# FT232RL_Model_with_USB-C.net
KiCad netlist of a schematic drawn in Altium Designer
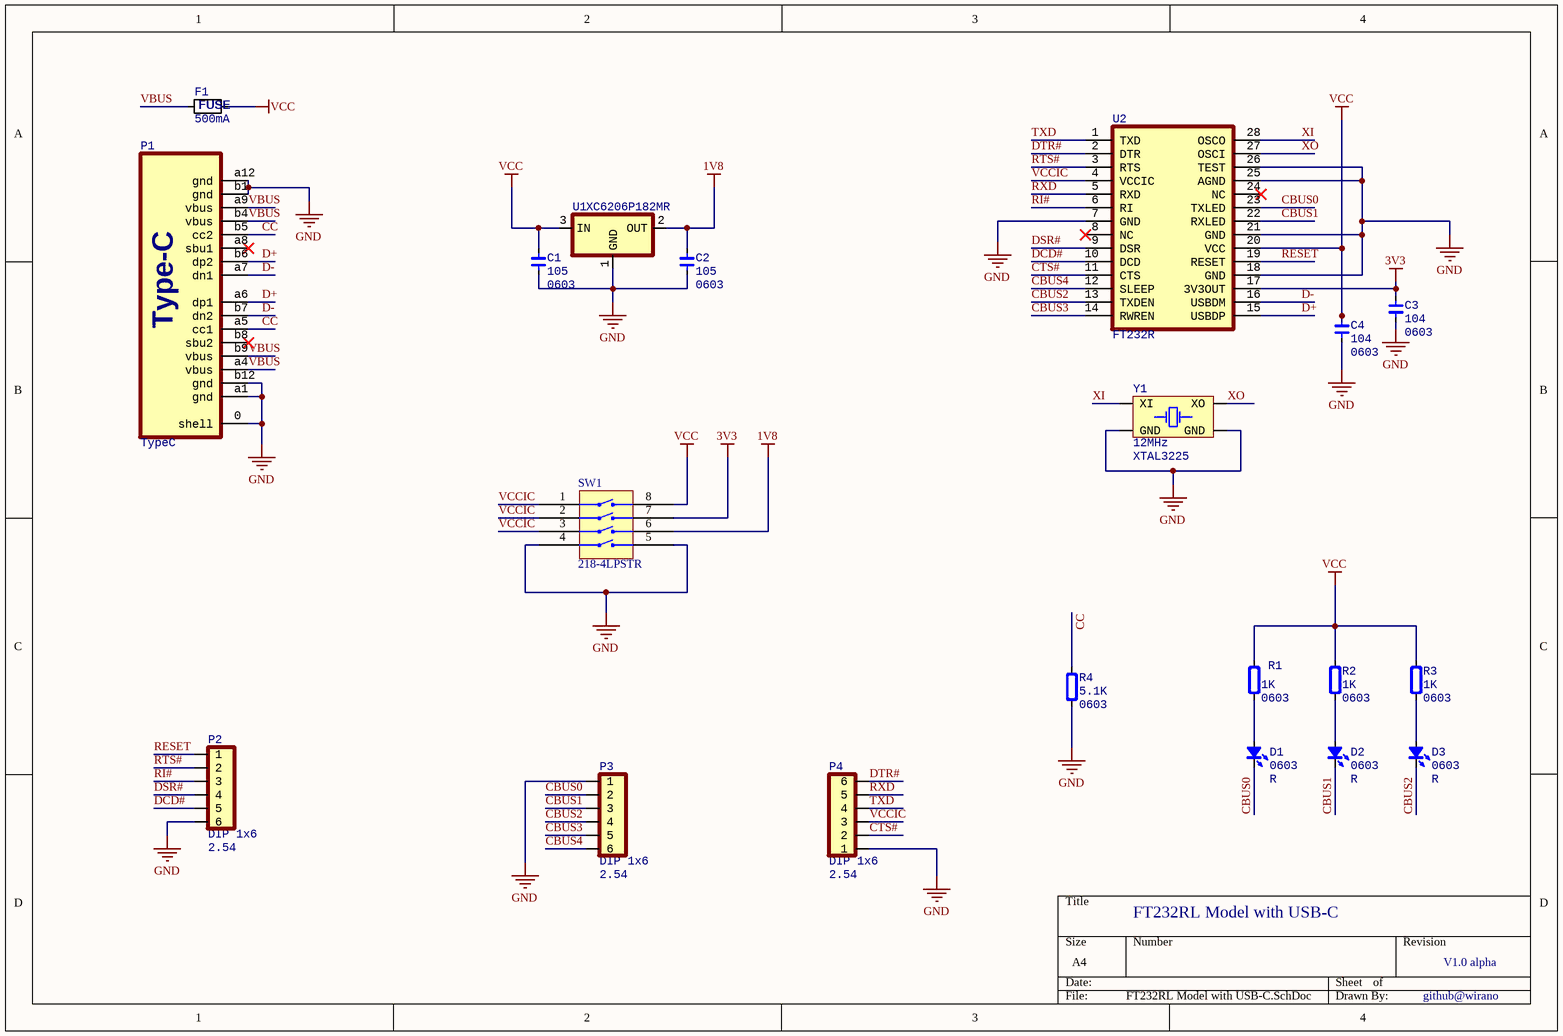
[diagram p0: FT232RL Model with USB-C.SchDoc]

(export (version "E")
  (design (tool "Eeschema 10.0.6"))
  (components
    (comp (ref "C1")
      (value "105")
      (footprint "CAP 0603/1608")
      (description "Capacitor")
      (fields (field (name "TYPE") "0603") (field (name "Comment") "C0603"))
      (libsource (lib "adlib") (part "Cap_0603"))
    )
    (comp (ref "C2")
      (value "105")
      (footprint "CAP 0603/1608")
      (description "Capacitor")
      (fields (field (name "TYPE") "0603") (field (name "Comment") "C0603"))
      (libsource (lib "adlib") (part "Cap_0603"))
    )
    (comp (ref "C3")
      (value "104")
      (footprint "CAP 0603/1608")
      (description "Capacitor")
      (fields (field (name "TYPE") "0603") (field (name "Comment") "C0603"))
      (libsource (lib "") (part "Cap_0603_1"))
    )
    (comp (ref "C4")
      (value "104")
      (footprint "CAP 0603/1608")
      (description "Capacitor")
      (fields (field (name "TYPE") "0603") (field (name "Comment") "C0603"))
      (libsource (lib "adlib") (part "Cap_0603"))
    )
    (comp (ref "D1")
      (value "R")
      (footprint "LED_0603_RED")
      (description "LED")
      (fields (field (name "TYPE") "0603"))
      (libsource (lib "adlib") (part "LED_0603"))
    )
    (comp (ref "D2")
      (value "R")
      (footprint "LED_0603_RED")
      (description "LED")
      (fields (field (name "TYPE") "0603"))
      (libsource (lib "adlib") (part "LED_0603"))
    )
    (comp (ref "D3")
      (value "R")
      (footprint "LED_0603_RED")
      (description "LED")
      (fields (field (name "TYPE") "0603"))
      (libsource (lib "adlib") (part "LED_0603"))
    )
    (comp (ref "F1")
      (value "500mA")
      (footprint "PPTC_0603")
      (description "resettable fuse")
      (libsource (lib "adlib") (part "Fuse"))
    )
    (comp (ref "P1")
      (value "TypeC")
      (footprint "USB_TypeC")
      (description "USB type-c cable")
      (libsource (lib "adlib") (part "USB_TypeC"))
    )
    (comp (ref "P2")
      (value "2.54")
      (footprint "HDR1X6_2.54_180")
      (description "Header")
      (fields (field (name "TYPE") "DIP 1x6") (field (name "Comment") "DIP 1x6"))
      (libsource (lib "adlib") (part "HDR1x6_2.54"))
    )
    (comp (ref "P3")
      (value "2.54")
      (footprint "HDR1X6_2.54_180")
      (description "Header")
      (fields (field (name "TYPE") "DIP 1x6") (field (name "Comment") "DIP 1x6"))
      (libsource (lib "adlib") (part "HDR1x6_2.54"))
    )
    (comp (ref "P4")
      (value "2.54")
      (footprint "HDR1X6_2.54_90")
      (description "Header")
      (fields (field (name "TYPE") "DIP 1x6") (field (name "Comment") "DIP 1x6"))
      (libsource (lib "") (part "HDR1x6_2.54_1"))
    )
    (comp (ref "R1")
      (value "1K")
      (footprint "RES 0603/1608")
      (description "SMT Resistor")
      (fields (field (name "TYPE") "0603") (field (name "Comment") "R0603"))
      (libsource (lib "adlib") (part "Res_0603"))
    )
    (comp (ref "R2")
      (value "1K")
      (footprint "RES 0603/1608")
      (description "SMT Resistor")
      (fields (field (name "TYPE") "0603") (field (name "Comment") "R0603"))
      (libsource (lib "adlib") (part "Res_0603"))
    )
    (comp (ref "R3")
      (value "1K")
      (footprint "RES 0603/1608")
      (description "SMT Resistor")
      (fields (field (name "TYPE") "0603") (field (name "Comment") "R0603"))
      (libsource (lib "adlib") (part "Res_0603"))
    )
    (comp (ref "R4")
      (value "5.1K")
      (footprint "RES 0603/1608")
      (description "SMT Resistor")
      (fields (field (name "TYPE") "0603") (field (name "Comment") "R0603"))
      (libsource (lib "adlib") (part "Res_0603"))
    )
    (comp (ref "SW1")
      (value "218-4LPSTR")
      (footprint "CTS 218-4LPJ")
      (description "SWITCH SLIDE DIP SPST 25MA 24V")
      (fields
        (field (name "MANUFACTURER") "CTS Electrocomponents")
        (field (name "LASTUPDATED") "20/1/4 周六 18:53:14")
      )
      (libsource (lib "Celestial Altium Library - altium_library") (part "DIP SW 4P"))
    )
    (comp (ref "U1")
      (value "XC6206P182MR")
      (footprint "_SOT23-3")
      (description "Regulator LDO")
      (libsource (lib "adlib") (part "XC6206P332MR"))
    )
    (comp (ref "U2")
      (value "FT232R")
      (footprint "_SSOP_E210_P0.65_28")
      (description "USB to UART Converter")
      (libsource (lib "adlib") (part "FT232R"))
    )
    (comp (ref "Y1")
      (value "12MHz")
      (footprint "XT_3225_4")
      (description "Crystal Oscillator")
      (fields (field (name "TYPE") "XTAL3225") (field (name "Comment") "XTAL3225"))
      (libsource (lib "adlib") (part "XTAL_3225_4P"))
    )
  )
  (nets
    (net (code "1") (name "/CBUS0") (class "Default")
      (node (ref "D1") (pin "2") (pinfunction "K_2") (pintype "passive"))
      (node (ref "P3") (pin "2") (pinfunction "2_2") (pintype "passive"))
      (node (ref "U2") (pin "23") (pinfunction "TXLED_23") (pintype "passive"))
    )
    (net (code "2") (name "/CBUS1") (class "Default")
      (node (ref "D2") (pin "2") (pinfunction "K_2") (pintype "passive"))
      (node (ref "P3") (pin "3") (pinfunction "3_3") (pintype "passive"))
      (node (ref "U2") (pin "22") (pinfunction "RXLED_22") (pintype "passive"))
    )
    (net (code "3") (name "/CBUS2") (class "Default")
      (node (ref "D3") (pin "2") (pinfunction "K_2") (pintype "passive"))
      (node (ref "P3") (pin "4") (pinfunction "4_4") (pintype "passive"))
      (node (ref "U2") (pin "13") (pinfunction "TXDEN_13") (pintype "passive"))
    )
    (net (code "4") (name "/CBUS3") (class "Default")
      (node (ref "P3") (pin "5") (pinfunction "5_5") (pintype "passive"))
      (node (ref "U2") (pin "14") (pinfunction "RWREN_14") (pintype "passive"))
    )
    (net (code "5") (name "/CBUS4") (class "Default")
      (node (ref "P3") (pin "6") (pinfunction "6_6") (pintype "passive"))
      (node (ref "U2") (pin "12") (pinfunction "SLEEP_12") (pintype "passive"))
    )
    (net (code "6") (name "/CC") (class "Default")
      (node (ref "P1") (pin "a5") (pinfunction "cc1_a5") (pintype "passive"))
      (node (ref "P1") (pin "b5") (pinfunction "cc2_b5") (pintype "passive"))
      (node (ref "R4") (pin "2") (pinfunction "2_2") (pintype "passive"))
    )
    (net (code "7") (name "/CTS#") (class "Default")
      (node (ref "P4") (pin "2") (pinfunction "2_2") (pintype "passive"))
      (node (ref "U2") (pin "11") (pinfunction "CTS_11") (pintype "passive"))
    )
    (net (code "8") (name "/D+") (class "Default")
      (node (ref "P1") (pin "a6") (pinfunction "dp1_a6") (pintype "passive"))
      (node (ref "P1") (pin "b6") (pinfunction "dp2_b6") (pintype "passive"))
      (node (ref "U2") (pin "15") (pinfunction "USBDP_15") (pintype "passive"))
    )
    (net (code "9") (name "/D-") (class "Default")
      (node (ref "P1") (pin "a7") (pinfunction "dn1_a7") (pintype "passive"))
      (node (ref "P1") (pin "b7") (pinfunction "dn2_b7") (pintype "passive"))
      (node (ref "U2") (pin "16") (pinfunction "USBDM_16") (pintype "passive"))
    )
    (net (code "10") (name "/DCD#") (class "Default")
      (node (ref "P2") (pin "5") (pinfunction "5_5") (pintype "passive"))
      (node (ref "U2") (pin "10") (pinfunction "DCD_10") (pintype "passive"))
    )
    (net (code "11") (name "/DSR#") (class "Default")
      (node (ref "P2") (pin "4") (pinfunction "4_4") (pintype "passive"))
      (node (ref "U2") (pin "9") (pinfunction "DSR_9") (pintype "passive"))
    )
    (net (code "12") (name "/DTR#") (class "Default")
      (node (ref "P4") (pin "6") (pinfunction "6_6") (pintype "passive"))
      (node (ref "U2") (pin "2") (pinfunction "DTR_2") (pintype "passive"))
    )
    (net (code "13") (name "/RESET") (class "Default")
      (node (ref "P2") (pin "1") (pinfunction "1_1") (pintype "passive"))
      (node (ref "U2") (pin "19") (pinfunction "RESET_19") (pintype "passive"))
    )
    (net (code "14") (name "/RI#") (class "Default")
      (node (ref "P2") (pin "3") (pinfunction "3_3") (pintype "passive"))
      (node (ref "U2") (pin "6") (pinfunction "RI_6") (pintype "passive"))
    )
    (net (code "15") (name "/RTS#") (class "Default")
      (node (ref "P2") (pin "2") (pinfunction "2_2") (pintype "passive"))
      (node (ref "U2") (pin "3") (pinfunction "RTS_3") (pintype "passive"))
    )
    (net (code "16") (name "/RXD") (class "Default")
      (node (ref "P4") (pin "5") (pinfunction "5_5") (pintype "passive"))
      (node (ref "U2") (pin "5") (pinfunction "RXD_5") (pintype "passive"))
    )
    (net (code "17") (name "/TXD") (class "Default")
      (node (ref "P4") (pin "4") (pinfunction "4_4") (pintype "passive"))
      (node (ref "U2") (pin "1") (pinfunction "TXD_1") (pintype "passive"))
    )
    (net (code "18") (name "/VBUS") (class "Default")
      (node (ref "F1") (pin "1") (pinfunction "1_1") (pintype "passive"))
      (node (ref "P1") (pin "a4") (pinfunction "vbus_a4") (pintype "passive"))
      (node (ref "P1") (pin "a9") (pinfunction "vbus_a9") (pintype "passive"))
      (node (ref "P1") (pin "b4") (pinfunction "vbus_b4") (pintype "passive"))
      (node (ref "P1") (pin "b9") (pinfunction "vbus_b9") (pintype "passive"))
    )
    (net (code "19") (name "/VCCIC") (class "Default")
      (node (ref "P4") (pin "3") (pinfunction "3_3") (pintype "passive"))
      (node (ref "SW1") (pin "1") (pinfunction "GND_1") (pintype "passive"))
      (node (ref "SW1") (pin "2") (pinfunction "GND_2") (pintype "passive"))
      (node (ref "SW1") (pin "3") (pinfunction "GND_3") (pintype "passive"))
      (node (ref "U2") (pin "4") (pinfunction "VCCIC_4") (pintype "passive"))
    )
    (net (code "20") (name "/XI") (class "Default")
      (node (ref "U2") (pin "28") (pinfunction "OSCO_28") (pintype "passive"))
      (node (ref "Y1") (pin "1") (pinfunction "XI_1") (pintype "passive"))
    )
    (net (code "21") (name "/XO") (class "Default")
      (node (ref "U2") (pin "27") (pinfunction "OSCI_27") (pintype "passive"))
      (node (ref "Y1") (pin "3") (pinfunction "XO_3") (pintype "passive"))
    )
    (net (code "22") (name "1V8") (class "Default")
      (node (ref "C2") (pin "2") (pinfunction "2_2") (pintype "passive"))
      (node (ref "SW1") (pin "6") (pinfunction "6_6") (pintype "passive"))
      (node (ref "U1") (pin "2") (pinfunction "OUT_2") (pintype "power_in"))
    )
    (net (code "23") (name "3V3") (class "Default")
      (node (ref "C3") (pin "1") (pinfunction "1_1") (pintype "passive"))
      (node (ref "SW1") (pin "7") (pinfunction "7_7") (pintype "passive"))
      (node (ref "U2") (pin "17") (pinfunction "3V3OUT_17") (pintype "passive"))
    )
    (net (code "24") (name "GND") (class "Default")
      (node (ref "C1") (pin "1") (pinfunction "1_1") (pintype "passive"))
      (node (ref "C2") (pin "1") (pinfunction "1_1") (pintype "passive"))
      (node (ref "C3") (pin "2") (pinfunction "2_2") (pintype "passive"))
      (node (ref "C4") (pin "1") (pinfunction "1_1") (pintype "passive"))
      (node (ref "P1") (pin "0") (pinfunction "shell_0") (pintype "passive"))
      (node (ref "P1") (pin "a1") (pinfunction "gnd_a1") (pintype "passive"))
      (node (ref "P1") (pin "a12") (pinfunction "gnd_a12") (pintype "passive"))
      (node (ref "P1") (pin "b1") (pinfunction "gnd_b1") (pintype "passive"))
      (node (ref "P1") (pin "b12") (pinfunction "gnd_b12") (pintype "passive"))
      (node (ref "P2") (pin "6") (pinfunction "6_6") (pintype "passive"))
      (node (ref "P3") (pin "1") (pinfunction "1_1") (pintype "passive"))
      (node (ref "P4") (pin "1") (pinfunction "1_1") (pintype "passive"))
      (node (ref "R4") (pin "1") (pinfunction "1_1") (pintype "passive"))
      (node (ref "SW1") (pin "4") (pinfunction "GND_4") (pintype "passive"))
      (node (ref "SW1") (pin "5") (pinfunction "5_5") (pintype "passive"))
      (node (ref "U1") (pin "1") (pinfunction "GND_1") (pintype "power_in"))
      (node (ref "U2") (pin "18") (pinfunction "GND_18") (pintype "passive"))
      (node (ref "U2") (pin "21") (pinfunction "GND_21") (pintype "passive"))
      (node (ref "U2") (pin "25") (pinfunction "AGND_25") (pintype "passive"))
      (node (ref "U2") (pin "26") (pinfunction "TEST_26") (pintype "passive"))
      (node (ref "U2") (pin "7") (pinfunction "GND_7") (pintype "passive"))
      (node (ref "Y1") (pin "2") (pinfunction "GND_2") (pintype "passive"))
      (node (ref "Y1") (pin "4") (pinfunction "GND_4") (pintype "passive"))
    )
    (net (code "25") (name "Net-(D1-A)") (class "Default")
      (node (ref "D1") (pin "1") (pinfunction "A_1") (pintype "passive"))
      (node (ref "R1") (pin "1") (pinfunction "1_1") (pintype "passive"))
    )
    (net (code "26") (name "Net-(D2-A)") (class "Default")
      (node (ref "D2") (pin "1") (pinfunction "A_1") (pintype "passive"))
      (node (ref "R2") (pin "1") (pinfunction "1_1") (pintype "passive"))
    )
    (net (code "27") (name "Net-(D3-A)") (class "Default")
      (node (ref "D3") (pin "1") (pinfunction "A_1") (pintype "passive"))
      (node (ref "R3") (pin "1") (pinfunction "1_1") (pintype "passive"))
    )
    (net (code "28") (name "VCC") (class "Default")
      (node (ref "C1") (pin "2") (pinfunction "2_2") (pintype "passive"))
      (node (ref "C4") (pin "2") (pinfunction "2_2") (pintype "passive"))
      (node (ref "F1") (pin "2") (pinfunction "2_2") (pintype "passive"))
      (node (ref "R1") (pin "2") (pinfunction "2_2") (pintype "passive"))
      (node (ref "R2") (pin "2") (pinfunction "2_2") (pintype "passive"))
      (node (ref "R3") (pin "2") (pinfunction "2_2") (pintype "passive"))
      (node (ref "SW1") (pin "8") (pinfunction "8_8") (pintype "passive"))
      (node (ref "U1") (pin "3") (pinfunction "IN_3") (pintype "power_in"))
      (node (ref "U2") (pin "20") (pinfunction "VCC_20") (pintype "passive"))
    )
    (net (code "29") (name "unconnected-(P1-sbu1-Pada8)") (class "Default")
      (node (ref "P1") (pin "a8") (pinfunction "sbu1_a8") (pintype "passive+no_connect"))
    )
    (net (code "30") (name "unconnected-(P1-sbu2-Padb8)") (class "Default")
      (node (ref "P1") (pin "b8") (pinfunction "sbu2_b8") (pintype "passive+no_connect"))
    )
    (net (code "31") (name "unconnected-(U2-NC-Pad8)") (class "Default")
      (node (ref "U2") (pin "8") (pinfunction "NC_8") (pintype "passive+no_connect"))
    )
    (net (code "32") (name "unconnected-(U2-NC-Pad24)") (class "Default")
      (node (ref "U2") (pin "24") (pinfunction "NC_24") (pintype "passive+no_connect"))
    )
  )
)
